# oven-controller-v3.net
KiCad netlist of a schematic drawn in EAGLE
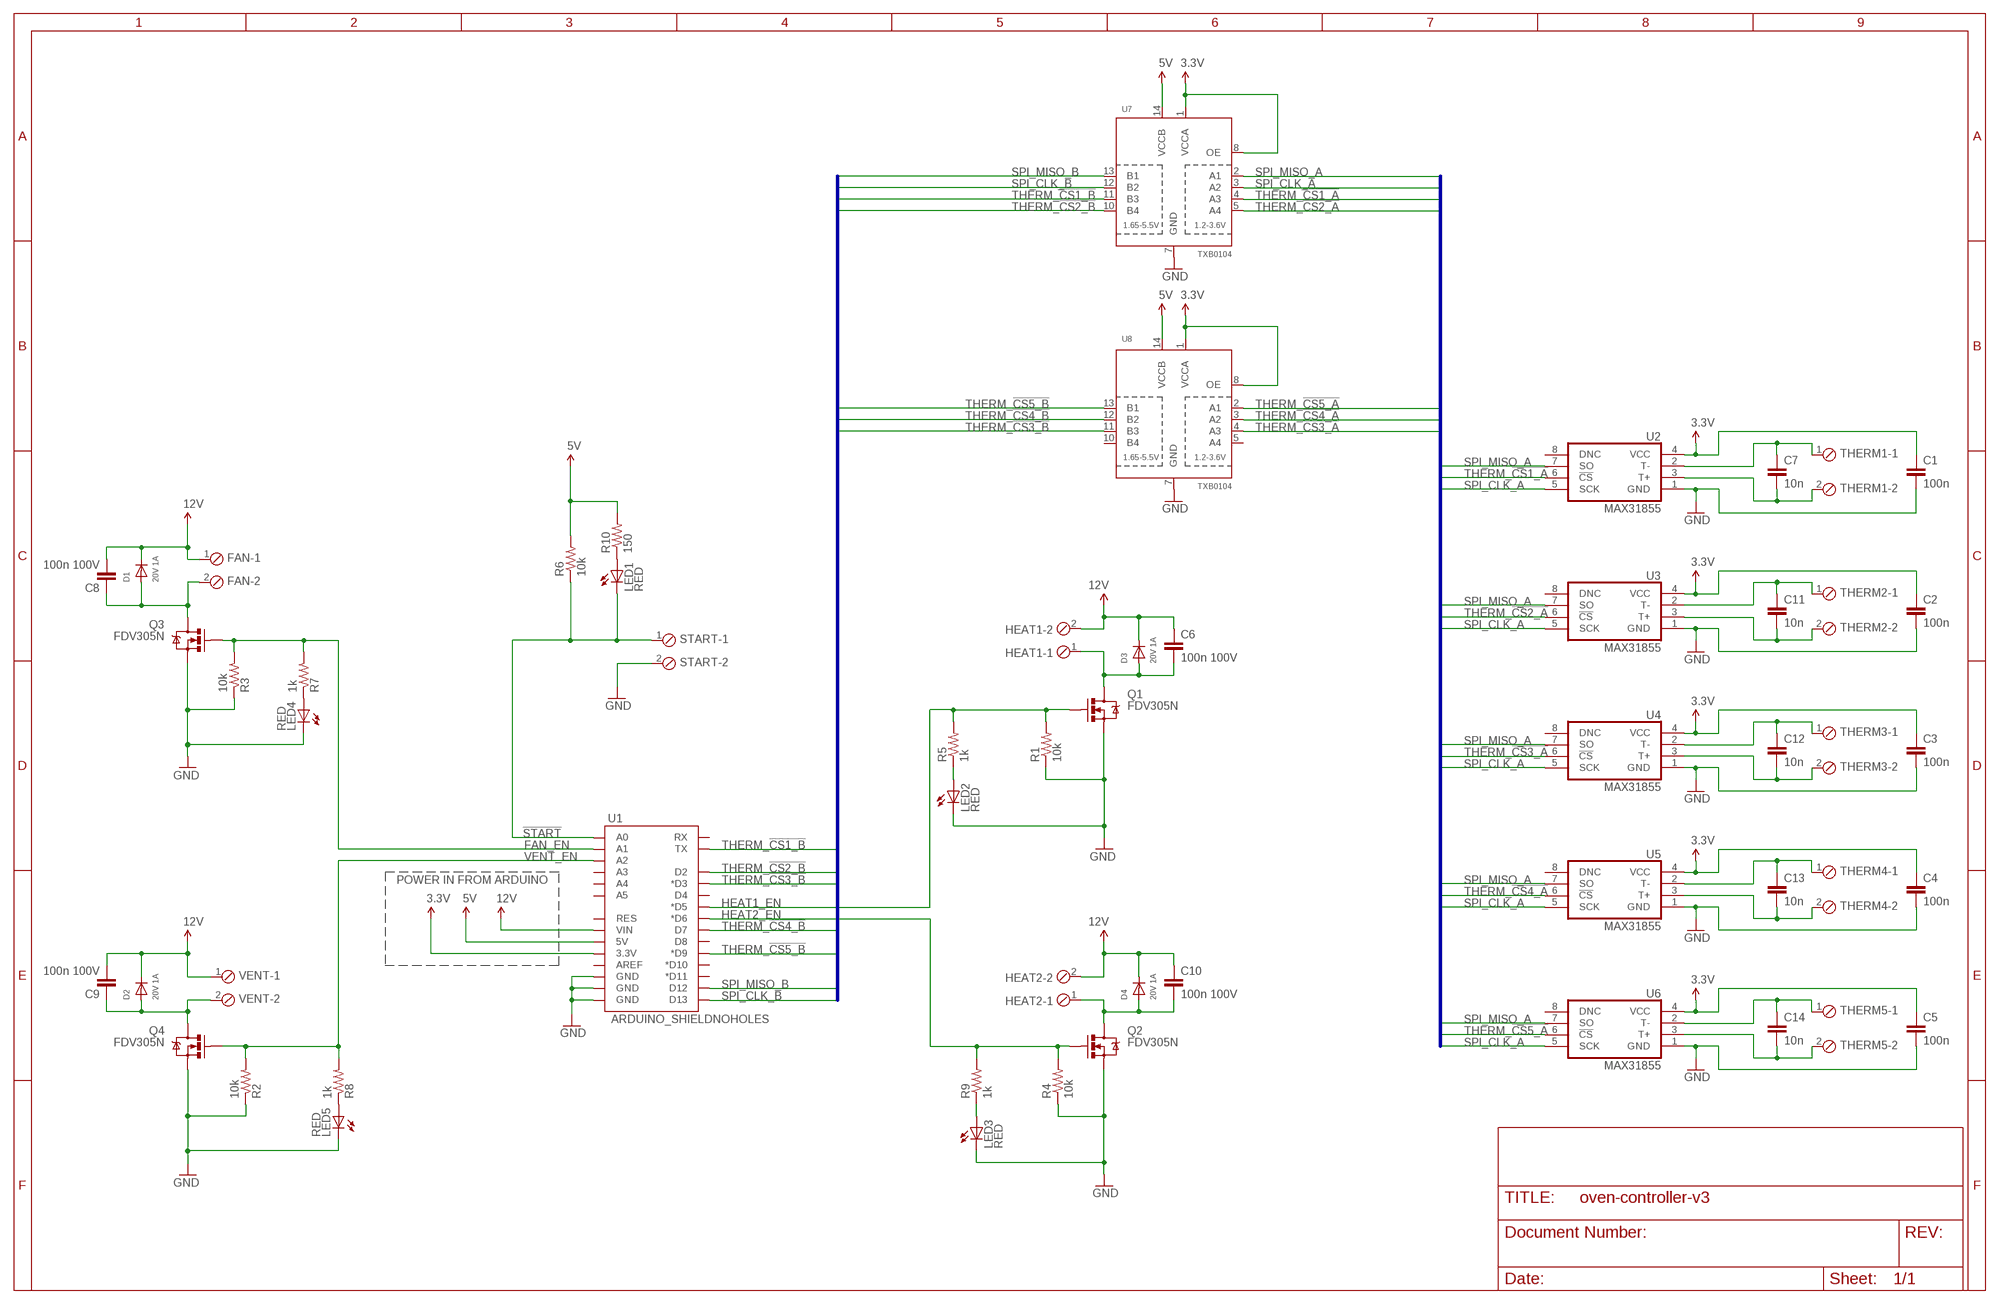
[diagram p0: schematic, sheet 1]

(export (version "E")
  (design (tool "Eeschema 10.0.6"))
  (components
    (comp (ref "C1")
      (value "100n")
      (footprint "eagle-import:C0603K")
      (libsource (lib "eagle-import") (part "C-EUC0603K"))
    )
    (comp (ref "C2")
      (value "100n")
      (footprint "eagle-import:C0603K")
      (libsource (lib "eagle-import") (part "C-EUC0603K"))
    )
    (comp (ref "C3")
      (value "100n")
      (footprint "eagle-import:C0603K")
      (libsource (lib "eagle-import") (part "C-EUC0603K"))
    )
    (comp (ref "C4")
      (value "100n")
      (footprint "eagle-import:C0603K")
      (libsource (lib "eagle-import") (part "C-EUC0603K"))
    )
    (comp (ref "C5")
      (value "100n")
      (footprint "eagle-import:C0603K")
      (libsource (lib "eagle-import") (part "C-EUC0603K"))
    )
    (comp (ref "C6")
      (value "100n 100V")
      (footprint "eagle-import:C0603K")
      (libsource (lib "eagle-import") (part "C-EUC0603K"))
    )
    (comp (ref "C7")
      (value "10n")
      (footprint "eagle-import:C0603K")
      (libsource (lib "eagle-import") (part "C-EUC0603K"))
    )
    (comp (ref "C8")
      (value "100n 100V")
      (footprint "eagle-import:C0603K")
      (libsource (lib "eagle-import") (part "C-EUC0603K"))
    )
    (comp (ref "C9")
      (value "100n 100V")
      (footprint "eagle-import:C0603K")
      (libsource (lib "eagle-import") (part "C-EUC0603K"))
    )
    (comp (ref "C10")
      (value "100n 100V")
      (footprint "eagle-import:C0603K")
      (libsource (lib "eagle-import") (part "C-EUC0603K"))
    )
    (comp (ref "C11")
      (value "10n")
      (footprint "eagle-import:C0603K")
      (libsource (lib "eagle-import") (part "C-EUC0603K"))
    )
    (comp (ref "C12")
      (value "10n")
      (footprint "eagle-import:C0603K")
      (libsource (lib "eagle-import") (part "C-EUC0603K"))
    )
    (comp (ref "C13")
      (value "10n")
      (footprint "eagle-import:C0603K")
      (libsource (lib "eagle-import") (part "C-EUC0603K"))
    )
    (comp (ref "C14")
      (value "10n")
      (footprint "eagle-import:C0603K")
      (libsource (lib "eagle-import") (part "C-EUC0603K"))
    )
    (comp (ref "D1")
      (value "20V 1A")
      (footprint "eagle-import:DO-214AC-SMA")
      (libsource (lib "eagle-import") (part "DIODE-DO214AC-SMA"))
    )
    (comp (ref "D2")
      (value "20V 1A")
      (footprint "eagle-import:DO-214AC-SMA")
      (libsource (lib "eagle-import") (part "DIODE-DO214AC-SMA"))
    )
    (comp (ref "D3")
      (value "20V 1A")
      (footprint "eagle-import:DO-214AC-SMA")
      (libsource (lib "eagle-import") (part "DIODE-DO214AC-SMA"))
    )
    (comp (ref "D4")
      (value "20V 1A")
      (footprint "eagle-import:DO-214AC-SMA")
      (libsource (lib "eagle-import") (part "DIODE-DO214AC-SMA"))
    )
    (comp (ref "FAN")
      (value "MPT2")
      (footprint "eagle-import:2POL254")
      (libsource (lib "eagle-import") (part "MPT2"))
    )
    (comp (ref "HEAT1")
      (value "MPT2")
      (footprint "eagle-import:2POL254")
      (libsource (lib "eagle-import") (part "MPT2"))
    )
    (comp (ref "HEAT2")
      (value "MPT2")
      (footprint "eagle-import:2POL254")
      (libsource (lib "eagle-import") (part "MPT2"))
    )
    (comp (ref "LED1")
      (value "RED")
      (footprint "eagle-import:LED-0603")
      (libsource (lib "eagle-import") (part "LED0603"))
    )
    (comp (ref "LED2")
      (value "RED")
      (footprint "eagle-import:LED-0603")
      (libsource (lib "eagle-import") (part "LED0603"))
    )
    (comp (ref "LED3")
      (value "RED")
      (footprint "eagle-import:LED-0603")
      (libsource (lib "eagle-import") (part "LED0603"))
    )
    (comp (ref "LED4")
      (value "RED")
      (footprint "eagle-import:LED-0603")
      (libsource (lib "eagle-import") (part "LED0603"))
    )
    (comp (ref "LED5")
      (value "RED")
      (footprint "eagle-import:LED-0603")
      (libsource (lib "eagle-import") (part "LED0603"))
    )
    (comp (ref "Q1")
      (value "FDV305N")
      (footprint "eagle-import:SOT23-3")
      (libsource (lib "eagle-import") (part "MOSFET-NCHANNELSMD"))
    )
    (comp (ref "Q2")
      (value "FDV305N")
      (footprint "eagle-import:SOT23-3")
      (libsource (lib "eagle-import") (part "MOSFET-NCHANNELSMD"))
    )
    (comp (ref "Q3")
      (value "FDV305N")
      (footprint "eagle-import:SOT23-3")
      (libsource (lib "eagle-import") (part "MOSFET-NCHANNELSMD"))
    )
    (comp (ref "Q4")
      (value "FDV305N")
      (footprint "eagle-import:SOT23-3")
      (libsource (lib "eagle-import") (part "MOSFET-NCHANNELSMD"))
    )
    (comp (ref "R1")
      (value "10k")
      (footprint "eagle-import:0603-C-NOSILK")
      (libsource (lib "eagle-import") (part "R-US_0603-C-NOSILK"))
    )
    (comp (ref "R2")
      (value "10k")
      (footprint "eagle-import:0603-C-NOSILK")
      (libsource (lib "eagle-import") (part "R-US_0603-C-NOSILK"))
    )
    (comp (ref "R3")
      (value "10k")
      (footprint "eagle-import:0603-C-NOSILK")
      (libsource (lib "eagle-import") (part "R-US_0603-C-NOSILK"))
    )
    (comp (ref "R4")
      (value "10k")
      (footprint "eagle-import:0603-C-NOSILK")
      (libsource (lib "eagle-import") (part "R-US_0603-C-NOSILK"))
    )
    (comp (ref "R5")
      (value "1k")
      (footprint "eagle-import:0603-C-NOSILK")
      (libsource (lib "eagle-import") (part "R-US_0603-C-NOSILK"))
    )
    (comp (ref "R6")
      (value "10k")
      (footprint "eagle-import:0603-C-NOSILK")
      (libsource (lib "eagle-import") (part "R-US_0603-C-NOSILK"))
    )
    (comp (ref "R7")
      (value "1k")
      (footprint "eagle-import:0603-C-NOSILK")
      (libsource (lib "eagle-import") (part "R-US_0603-C-NOSILK"))
    )
    (comp (ref "R8")
      (value "1k")
      (footprint "eagle-import:0603-C-NOSILK")
      (libsource (lib "eagle-import") (part "R-US_0603-C-NOSILK"))
    )
    (comp (ref "R9")
      (value "1k")
      (footprint "eagle-import:0603-C-NOSILK")
      (libsource (lib "eagle-import") (part "R-US_0603-C-NOSILK"))
    )
    (comp (ref "R10")
      (value "150")
      (footprint "eagle-import:0603-C-NOSILK")
      (libsource (lib "eagle-import") (part "R-US_0603-C-NOSILK"))
    )
    (comp (ref "START")
      (value "MPT2")
      (footprint "eagle-import:2POL254")
      (libsource (lib "eagle-import") (part "MPT2"))
    )
    (comp (ref "THERM1")
      (value "MPT2")
      (footprint "eagle-import:2POL254")
      (libsource (lib "eagle-import") (part "MPT2"))
    )
    (comp (ref "THERM2")
      (value "MPT2")
      (footprint "eagle-import:2POL254")
      (libsource (lib "eagle-import") (part "MPT2"))
    )
    (comp (ref "THERM3")
      (value "MPT2")
      (footprint "eagle-import:2POL254")
      (libsource (lib "eagle-import") (part "MPT2"))
    )
    (comp (ref "THERM4")
      (value "MPT2")
      (footprint "eagle-import:2POL254")
      (libsource (lib "eagle-import") (part "MPT2"))
    )
    (comp (ref "THERM5")
      (value "MPT2")
      (footprint "eagle-import:2POL254")
      (libsource (lib "eagle-import") (part "MPT2"))
    )
    (comp (ref "U1")
      (value "ARDUINO_SHIELDNOHOLES")
      (footprint "eagle-import:DUEMILANOVE_SHIELD_NOHOLES")
      (libsource (lib "eagle-import") (part "ARDUINO_SHIELDNOHOLES"))
    )
    (comp (ref "U2")
      (value "MAX31855")
      (footprint "eagle-import:SO-8")
      (libsource (lib "eagle-import") (part "IC_MAX31855-SO-8"))
    )
    (comp (ref "U3")
      (value "MAX31855")
      (footprint "eagle-import:SO-8")
      (libsource (lib "eagle-import") (part "IC_MAX31855-SO-8"))
    )
    (comp (ref "U4")
      (value "MAX31855")
      (footprint "eagle-import:SO-8")
      (libsource (lib "eagle-import") (part "IC_MAX31855-SO-8"))
    )
    (comp (ref "U5")
      (value "MAX31855")
      (footprint "eagle-import:SO-8")
      (libsource (lib "eagle-import") (part "IC_MAX31855-SO-8"))
    )
    (comp (ref "U6")
      (value "MAX31855")
      (footprint "eagle-import:SO-8")
      (libsource (lib "eagle-import") (part "IC_MAX31855-SO-8"))
    )
    (comp (ref "U7")
      (value "TXB0104")
      (footprint "eagle-import:TSSOP14")
      (libsource (lib "eagle-import") (part "TXB0104PWR"))
    )
    (comp (ref "U8")
      (value "TXB0104")
      (footprint "eagle-import:TSSOP14")
      (libsource (lib "eagle-import") (part "TXB0104PWR"))
    )
    (comp (ref "VENT")
      (value "MPT2")
      (footprint "eagle-import:2POL254")
      (libsource (lib "eagle-import") (part "MPT2"))
    )
  )
  (nets
    (net (code "1") (name "/FAN_EN") (class "Default")
      (node (ref "Q3") (pin "1") (pinfunction "G_1") (pintype "passive"))
      (node (ref "R3") (pin "2") (pinfunction "2_2") (pintype "passive"))
      (node (ref "R7") (pin "2") (pinfunction "2_2") (pintype "passive"))
      (node (ref "U1") (pin "A1") (pinfunction "A1_A1") (pintype "bidirectional"))
    )
    (net (code "2") (name "/HEAT1_EN") (class "Default")
      (node (ref "Q1") (pin "1") (pinfunction "G_1") (pintype "passive"))
      (node (ref "R1") (pin "2") (pinfunction "2_2") (pintype "passive"))
      (node (ref "R5") (pin "2") (pinfunction "2_2") (pintype "passive"))
      (node (ref "U1") (pin "D5") (pinfunction "*D5_D5") (pintype "bidirectional"))
    )
    (net (code "3") (name "/HEAT2_EN") (class "Default")
      (node (ref "Q2") (pin "1") (pinfunction "G_1") (pintype "passive"))
      (node (ref "R4") (pin "2") (pinfunction "2_2") (pintype "passive"))
      (node (ref "R9") (pin "2") (pinfunction "2_2") (pintype "passive"))
      (node (ref "U1") (pin "D6") (pinfunction "*D6_D6") (pintype "bidirectional"))
    )
    (net (code "4") (name "/SPI_CLK_A") (class "Default")
      (node (ref "U2") (pin "5") (pinfunction "SCK_5") (pintype "input"))
      (node (ref "U3") (pin "5") (pinfunction "SCK_5") (pintype "input"))
      (node (ref "U4") (pin "5") (pinfunction "SCK_5") (pintype "input"))
      (node (ref "U5") (pin "5") (pinfunction "SCK_5") (pintype "input"))
      (node (ref "U6") (pin "5") (pinfunction "SCK_5") (pintype "input"))
      (node (ref "U7") (pin "3") (pinfunction "A2_3") (pintype "bidirectional"))
    )
    (net (code "5") (name "/SPI_CLK_B") (class "Default")
      (node (ref "U1") (pin "D13") (pinfunction "D13_D13") (pintype "bidirectional"))
      (node (ref "U7") (pin "12") (pinfunction "B2_12") (pintype "bidirectional"))
    )
    (net (code "6") (name "/SPI_MISO_A") (class "Default")
      (node (ref "U2") (pin "7") (pinfunction "SO_7") (pintype "output"))
      (node (ref "U3") (pin "7") (pinfunction "SO_7") (pintype "output"))
      (node (ref "U4") (pin "7") (pinfunction "SO_7") (pintype "output"))
      (node (ref "U5") (pin "7") (pinfunction "SO_7") (pintype "output"))
      (node (ref "U6") (pin "7") (pinfunction "SO_7") (pintype "output"))
      (node (ref "U7") (pin "2") (pinfunction "A1_2") (pintype "bidirectional"))
    )
    (net (code "7") (name "/SPI_MISO_B") (class "Default")
      (node (ref "U1") (pin "D12") (pinfunction "D12_D12") (pintype "bidirectional"))
      (node (ref "U7") (pin "13") (pinfunction "B1_13") (pintype "bidirectional"))
    )
    (net (code "8") (name "/THERM_~{CS1_A}") (class "Default")
      (node (ref "U2") (pin "6") (pinfunction "~{CS}_6") (pintype "input"))
      (node (ref "U7") (pin "4") (pinfunction "A3_4") (pintype "bidirectional"))
    )
    (net (code "9") (name "/THERM_~{CS1_B}") (class "Default")
      (node (ref "U1") (pin "TX") (pinfunction "TX_TX") (pintype "bidirectional"))
      (node (ref "U7") (pin "11") (pinfunction "B3_11") (pintype "bidirectional"))
    )
    (net (code "10") (name "/THERM_~{CS2_A}") (class "Default")
      (node (ref "U3") (pin "6") (pinfunction "~{CS}_6") (pintype "input"))
      (node (ref "U7") (pin "5") (pinfunction "A4_5") (pintype "bidirectional"))
    )
    (net (code "11") (name "/THERM_~{CS2_B}") (class "Default")
      (node (ref "U1") (pin "D2") (pinfunction "D2_D2") (pintype "bidirectional"))
      (node (ref "U7") (pin "10") (pinfunction "B4_10") (pintype "bidirectional"))
    )
    (net (code "12") (name "/THERM_~{CS3_A}") (class "Default")
      (node (ref "U4") (pin "6") (pinfunction "~{CS}_6") (pintype "input"))
      (node (ref "U8") (pin "4") (pinfunction "A3_4") (pintype "bidirectional"))
    )
    (net (code "13") (name "/THERM_~{CS3_B}") (class "Default")
      (node (ref "U1") (pin "D3") (pinfunction "*D3_D3") (pintype "bidirectional"))
      (node (ref "U8") (pin "11") (pinfunction "B3_11") (pintype "bidirectional"))
    )
    (net (code "14") (name "/THERM_~{CS4_A}") (class "Default")
      (node (ref "U5") (pin "6") (pinfunction "~{CS}_6") (pintype "input"))
      (node (ref "U8") (pin "3") (pinfunction "A2_3") (pintype "bidirectional"))
    )
    (net (code "15") (name "/THERM_~{CS4_B}") (class "Default")
      (node (ref "U1") (pin "D7") (pinfunction "D7_D7") (pintype "bidirectional"))
      (node (ref "U8") (pin "12") (pinfunction "B2_12") (pintype "bidirectional"))
    )
    (net (code "16") (name "/THERM_~{CS5_A}") (class "Default")
      (node (ref "U6") (pin "6") (pinfunction "~{CS}_6") (pintype "input"))
      (node (ref "U8") (pin "2") (pinfunction "A1_2") (pintype "bidirectional"))
    )
    (net (code "17") (name "/THERM_~{CS5_B}") (class "Default")
      (node (ref "U1") (pin "D9") (pinfunction "*D9_D9") (pintype "bidirectional"))
      (node (ref "U8") (pin "13") (pinfunction "B1_13") (pintype "bidirectional"))
    )
    (net (code "18") (name "/VENT_EN") (class "Default")
      (node (ref "Q4") (pin "1") (pinfunction "G_1") (pintype "passive"))
      (node (ref "R2") (pin "2") (pinfunction "2_2") (pintype "passive"))
      (node (ref "R8") (pin "2") (pinfunction "2_2") (pintype "passive"))
      (node (ref "U1") (pin "A2") (pinfunction "A2_A2") (pintype "bidirectional"))
    )
    (net (code "19") (name "/~{START}") (class "Default")
      (node (ref "LED1") (pin "C") (pinfunction "C_C") (pintype "passive"))
      (node (ref "R6") (pin "1") (pinfunction "1_1") (pintype "passive"))
      (node (ref "START") (pin "1") (pinfunction "1_1") (pintype "passive"))
      (node (ref "U1") (pin "A0") (pinfunction "A0_A0") (pintype "bidirectional"))
    )
    (net (code "20") (name "3.3V") (class "Default")
      (node (ref "C1") (pin "1") (pinfunction "1_1") (pintype "passive"))
      (node (ref "C2") (pin "1") (pinfunction "1_1") (pintype "passive"))
      (node (ref "C3") (pin "1") (pinfunction "1_1") (pintype "passive"))
      (node (ref "C4") (pin "1") (pinfunction "1_1") (pintype "passive"))
      (node (ref "C5") (pin "1") (pinfunction "1_1") (pintype "passive"))
      (node (ref "U1") (pin "3.3V") (pinfunction "3.3V_3.3V") (pintype "bidirectional"))
      (node (ref "U2") (pin "4") (pinfunction "VCC_4") (pintype "power_in"))
      (node (ref "U3") (pin "4") (pinfunction "VCC_4") (pintype "power_in"))
      (node (ref "U4") (pin "4") (pinfunction "VCC_4") (pintype "power_in"))
      (node (ref "U5") (pin "4") (pinfunction "VCC_4") (pintype "power_in"))
      (node (ref "U6") (pin "4") (pinfunction "VCC_4") (pintype "power_in"))
      (node (ref "U7") (pin "1") (pinfunction "VCCA_1") (pintype "bidirectional"))
      (node (ref "U7") (pin "8") (pinfunction "OE_8") (pintype "bidirectional"))
      (node (ref "U8") (pin "1") (pinfunction "VCCA_1") (pintype "bidirectional"))
      (node (ref "U8") (pin "8") (pinfunction "OE_8") (pintype "bidirectional"))
    )
    (net (code "21") (name "5V") (class "Default")
      (node (ref "R10") (pin "2") (pinfunction "2_2") (pintype "passive"))
      (node (ref "R6") (pin "2") (pinfunction "2_2") (pintype "passive"))
      (node (ref "U1") (pin "5V") (pinfunction "5V_5V") (pintype "bidirectional"))
      (node (ref "U7") (pin "14") (pinfunction "VCCB_14") (pintype "bidirectional"))
      (node (ref "U8") (pin "14") (pinfunction "VCCB_14") (pintype "bidirectional"))
    )
    (net (code "22") (name "12V") (class "Default")
      (node (ref "C10") (pin "1") (pinfunction "1_1") (pintype "passive"))
      (node (ref "C6") (pin "1") (pinfunction "1_1") (pintype "passive"))
      (node (ref "C8") (pin "2") (pinfunction "2_2") (pintype "passive"))
      (node (ref "C9") (pin "2") (pinfunction "2_2") (pintype "passive"))
      (node (ref "D1") (pin "C") (pinfunction "C_C") (pintype "passive"))
      (node (ref "D2") (pin "C") (pinfunction "C_C") (pintype "passive"))
      (node (ref "D3") (pin "C") (pinfunction "C_C") (pintype "passive"))
      (node (ref "D4") (pin "C") (pinfunction "C_C") (pintype "passive"))
      (node (ref "FAN") (pin "1") (pinfunction "1_1") (pintype "passive"))
      (node (ref "HEAT1") (pin "2") (pinfunction "1_2") (pintype "passive"))
      (node (ref "HEAT2") (pin "2") (pinfunction "1_2") (pintype "passive"))
      (node (ref "U1") (pin "VIN") (pinfunction "VIN_VIN") (pintype "bidirectional"))
      (node (ref "VENT") (pin "1") (pinfunction "1_1") (pintype "passive"))
    )
    (net (code "23") (name "GND") (class "Default")
      (node (ref "C1") (pin "2") (pinfunction "2_2") (pintype "passive"))
      (node (ref "C2") (pin "2") (pinfunction "2_2") (pintype "passive"))
      (node (ref "C3") (pin "2") (pinfunction "2_2") (pintype "passive"))
      (node (ref "C4") (pin "2") (pinfunction "2_2") (pintype "passive"))
      (node (ref "C5") (pin "2") (pinfunction "2_2") (pintype "passive"))
      (node (ref "LED2") (pin "C") (pinfunction "C_C") (pintype "passive"))
      (node (ref "LED3") (pin "C") (pinfunction "C_C") (pintype "passive"))
      (node (ref "LED4") (pin "C") (pinfunction "C_C") (pintype "passive"))
      (node (ref "LED5") (pin "C") (pinfunction "C_C") (pintype "passive"))
      (node (ref "Q1") (pin "2") (pinfunction "S_2") (pintype "passive"))
      (node (ref "Q2") (pin "2") (pinfunction "S_2") (pintype "passive"))
      (node (ref "Q3") (pin "2") (pinfunction "S_2") (pintype "passive"))
      (node (ref "Q4") (pin "2") (pinfunction "S_2") (pintype "passive"))
      (node (ref "R1") (pin "1") (pinfunction "1_1") (pintype "passive"))
      (node (ref "R2") (pin "1") (pinfunction "1_1") (pintype "passive"))
      (node (ref "R3") (pin "1") (pinfunction "1_1") (pintype "passive"))
      (node (ref "R4") (pin "1") (pinfunction "1_1") (pintype "passive"))
      (node (ref "START") (pin "2") (pinfunction "1_2") (pintype "passive"))
      (node (ref "U1") (pin "GND@0") (pinfunction "GND_GND@0") (pintype "bidirectional"))
      (node (ref "U1") (pin "GND@1") (pinfunction "GND_GND@1") (pintype "bidirectional"))
      (node (ref "U1") (pin "GND@2") (pinfunction "GND_GND@2") (pintype "bidirectional"))
      (node (ref "U2") (pin "1") (pinfunction "GND_1") (pintype "power_in"))
      (node (ref "U3") (pin "1") (pinfunction "GND_1") (pintype "power_in"))
      (node (ref "U4") (pin "1") (pinfunction "GND_1") (pintype "power_in"))
      (node (ref "U5") (pin "1") (pinfunction "GND_1") (pintype "power_in"))
      (node (ref "U6") (pin "1") (pinfunction "GND_1") (pintype "power_in"))
      (node (ref "U7") (pin "7") (pinfunction "GND_7") (pintype "bidirectional"))
      (node (ref "U8") (pin "7") (pinfunction "GND_7") (pintype "bidirectional"))
    )
    (net (code "24") (name "Net-(FANB-1)") (class "Default")
      (node (ref "C8") (pin "1") (pinfunction "1_1") (pintype "passive"))
      (node (ref "D1") (pin "A") (pinfunction "A_A") (pintype "passive"))
      (node (ref "FAN") (pin "2") (pinfunction "1_2") (pintype "passive"))
      (node (ref "Q3") (pin "3") (pinfunction "D_3") (pintype "passive"))
    )
    (net (code "25") (name "Net-(LED1-PadA)") (class "Default")
      (node (ref "LED1") (pin "A") (pinfunction "A_A") (pintype "passive"))
      (node (ref "R10") (pin "1") (pinfunction "1_1") (pintype "passive"))
    )
    (net (code "26") (name "Net-(LED2-PadA)") (class "Default")
      (node (ref "LED2") (pin "A") (pinfunction "A_A") (pintype "passive"))
      (node (ref "R5") (pin "1") (pinfunction "1_1") (pintype "passive"))
    )
    (net (code "27") (name "Net-(LED3-PadA)") (class "Default")
      (node (ref "LED3") (pin "A") (pinfunction "A_A") (pintype "passive"))
      (node (ref "R9") (pin "1") (pinfunction "1_1") (pintype "passive"))
    )
    (net (code "28") (name "Net-(LED4-PadA)") (class "Default")
      (node (ref "LED4") (pin "A") (pinfunction "A_A") (pintype "passive"))
      (node (ref "R7") (pin "1") (pinfunction "1_1") (pintype "passive"))
    )
    (net (code "29") (name "Net-(LED5-PadA)") (class "Default")
      (node (ref "LED5") (pin "A") (pinfunction "A_A") (pintype "passive"))
      (node (ref "R8") (pin "1") (pinfunction "1_1") (pintype "passive"))
    )
    (net (code "30") (name "Net-(Q1-D)") (class "Default")
      (node (ref "C6") (pin "2") (pinfunction "2_2") (pintype "passive"))
      (node (ref "D3") (pin "A") (pinfunction "A_A") (pintype "passive"))
      (node (ref "HEAT1") (pin "1") (pinfunction "1_1") (pintype "passive"))
      (node (ref "Q1") (pin "3") (pinfunction "D_3") (pintype "passive"))
    )
    (net (code "31") (name "Net-(Q2-D)") (class "Default")
      (node (ref "C10") (pin "2") (pinfunction "2_2") (pintype "passive"))
      (node (ref "D4") (pin "A") (pinfunction "A_A") (pintype "passive"))
      (node (ref "HEAT2") (pin "1") (pinfunction "1_1") (pintype "passive"))
      (node (ref "Q2") (pin "3") (pinfunction "D_3") (pintype "passive"))
    )
    (net (code "32") (name "Net-(Q4-D)") (class "Default")
      (node (ref "C9") (pin "1") (pinfunction "1_1") (pintype "passive"))
      (node (ref "D2") (pin "A") (pinfunction "A_A") (pintype "passive"))
      (node (ref "Q4") (pin "3") (pinfunction "D_3") (pintype "passive"))
      (node (ref "VENT") (pin "2") (pinfunction "1_2") (pintype "passive"))
    )
    (net (code "33") (name "Net-(THERM1B-1)") (class "Default")
      (node (ref "C7") (pin "2") (pinfunction "2_2") (pintype "passive"))
      (node (ref "THERM1") (pin "2") (pinfunction "1_2") (pintype "passive"))
      (node (ref "U2") (pin "3") (pinfunction "T+_3") (pintype "input"))
    )
    (net (code "34") (name "Net-(THERM2B-1)") (class "Default")
      (node (ref "C11") (pin "2") (pinfunction "2_2") (pintype "passive"))
      (node (ref "THERM2") (pin "2") (pinfunction "1_2") (pintype "passive"))
      (node (ref "U3") (pin "3") (pinfunction "T+_3") (pintype "input"))
    )
    (net (code "35") (name "Net-(THERM3B-1)") (class "Default")
      (node (ref "C12") (pin "2") (pinfunction "2_2") (pintype "passive"))
      (node (ref "THERM3") (pin "2") (pinfunction "1_2") (pintype "passive"))
      (node (ref "U4") (pin "3") (pinfunction "T+_3") (pintype "input"))
    )
    (net (code "36") (name "Net-(THERM4B-1)") (class "Default")
      (node (ref "C13") (pin "2") (pinfunction "2_2") (pintype "passive"))
      (node (ref "THERM4") (pin "2") (pinfunction "1_2") (pintype "passive"))
      (node (ref "U5") (pin "3") (pinfunction "T+_3") (pintype "input"))
    )
    (net (code "37") (name "Net-(THERM5B-1)") (class "Default")
      (node (ref "C14") (pin "2") (pinfunction "2_2") (pintype "passive"))
      (node (ref "THERM5") (pin "2") (pinfunction "1_2") (pintype "passive"))
      (node (ref "U6") (pin "3") (pinfunction "T+_3") (pintype "input"))
    )
    (net (code "38") (name "Net-(U2-T-)") (class "Default")
      (node (ref "C7") (pin "1") (pinfunction "1_1") (pintype "passive"))
      (node (ref "THERM1") (pin "1") (pinfunction "1_1") (pintype "passive"))
      (node (ref "U2") (pin "2") (pinfunction "T-_2") (pintype "input"))
    )
    (net (code "39") (name "Net-(U3-T-)") (class "Default")
      (node (ref "C11") (pin "1") (pinfunction "1_1") (pintype "passive"))
      (node (ref "THERM2") (pin "1") (pinfunction "1_1") (pintype "passive"))
      (node (ref "U3") (pin "2") (pinfunction "T-_2") (pintype "input"))
    )
    (net (code "40") (name "Net-(U4-T-)") (class "Default")
      (node (ref "C12") (pin "1") (pinfunction "1_1") (pintype "passive"))
      (node (ref "THERM3") (pin "1") (pinfunction "1_1") (pintype "passive"))
      (node (ref "U4") (pin "2") (pinfunction "T-_2") (pintype "input"))
    )
    (net (code "41") (name "Net-(U5-T-)") (class "Default")
      (node (ref "C13") (pin "1") (pinfunction "1_1") (pintype "passive"))
      (node (ref "THERM4") (pin "1") (pinfunction "1_1") (pintype "passive"))
      (node (ref "U5") (pin "2") (pinfunction "T-_2") (pintype "input"))
    )
    (net (code "42") (name "Net-(U6-T-)") (class "Default")
      (node (ref "C14") (pin "1") (pinfunction "1_1") (pintype "passive"))
      (node (ref "THERM5") (pin "1") (pinfunction "1_1") (pintype "passive"))
      (node (ref "U6") (pin "2") (pinfunction "T-_2") (pintype "input"))
    )
    (net (code "43") (name "unconnected-(U1-*D10-PadD10)") (class "Default")
      (node (ref "U1") (pin "D10") (pinfunction "*D10_D10") (pintype "bidirectional"))
    )
    (net (code "44") (name "unconnected-(U1-*D11-PadD11)") (class "Default")
      (node (ref "U1") (pin "D11") (pinfunction "*D11_D11") (pintype "bidirectional"))
    )
    (net (code "45") (name "unconnected-(U1-PadA3)") (class "Default")
      (node (ref "U1") (pin "A3") (pinfunction "A3_A3") (pintype "bidirectional"))
    )
    (net (code "46") (name "unconnected-(U1-PadA4)") (class "Default")
      (node (ref "U1") (pin "A4") (pinfunction "A4_A4") (pintype "bidirectional"))
    )
    (net (code "47") (name "unconnected-(U1-PadA5)") (class "Default")
      (node (ref "U1") (pin "A5") (pinfunction "A5_A5") (pintype "bidirectional"))
    )
    (net (code "48") (name "unconnected-(U1-PadAREF)") (class "Default")
      (node (ref "U1") (pin "AREF") (pinfunction "AREF_AREF") (pintype "bidirectional"))
    )
    (net (code "49") (name "unconnected-(U1-PadD4)") (class "Default")
      (node (ref "U1") (pin "D4") (pinfunction "D4_D4") (pintype "bidirectional"))
    )
    (net (code "50") (name "unconnected-(U1-PadD8)") (class "Default")
      (node (ref "U1") (pin "D8") (pinfunction "D8_D8") (pintype "bidirectional"))
    )
    (net (code "51") (name "unconnected-(U1-PadRES)") (class "Default")
      (node (ref "U1") (pin "RES") (pinfunction "RES_RES") (pintype "bidirectional"))
    )
    (net (code "52") (name "unconnected-(U1-PadRX)") (class "Default")
      (node (ref "U1") (pin "RX") (pinfunction "RX_RX") (pintype "bidirectional"))
    )
    (net (code "53") (name "unconnected-(U2-DNC-Pad8)") (class "Default")
      (node (ref "U2") (pin "8") (pinfunction "DNC_8") (pintype "no_connect"))
    )
    (net (code "54") (name "unconnected-(U3-DNC-Pad8)") (class "Default")
      (node (ref "U3") (pin "8") (pinfunction "DNC_8") (pintype "no_connect"))
    )
    (net (code "55") (name "unconnected-(U4-DNC-Pad8)") (class "Default")
      (node (ref "U4") (pin "8") (pinfunction "DNC_8") (pintype "no_connect"))
    )
    (net (code "56") (name "unconnected-(U5-DNC-Pad8)") (class "Default")
      (node (ref "U5") (pin "8") (pinfunction "DNC_8") (pintype "no_connect"))
    )
    (net (code "57") (name "unconnected-(U6-DNC-Pad8)") (class "Default")
      (node (ref "U6") (pin "8") (pinfunction "DNC_8") (pintype "no_connect"))
    )
    (net (code "58") (name "unconnected-(U8-A4-Pad5)") (class "Default")
      (node (ref "U8") (pin "5") (pinfunction "A4_5") (pintype "bidirectional"))
    )
    (net (code "59") (name "unconnected-(U8-B4-Pad10)") (class "Default")
      (node (ref "U8") (pin "10") (pinfunction "B4_10") (pintype "bidirectional"))
    )
  )
)
